# Power.net
KiCad netlist of a schematic drawn in Altium Designer
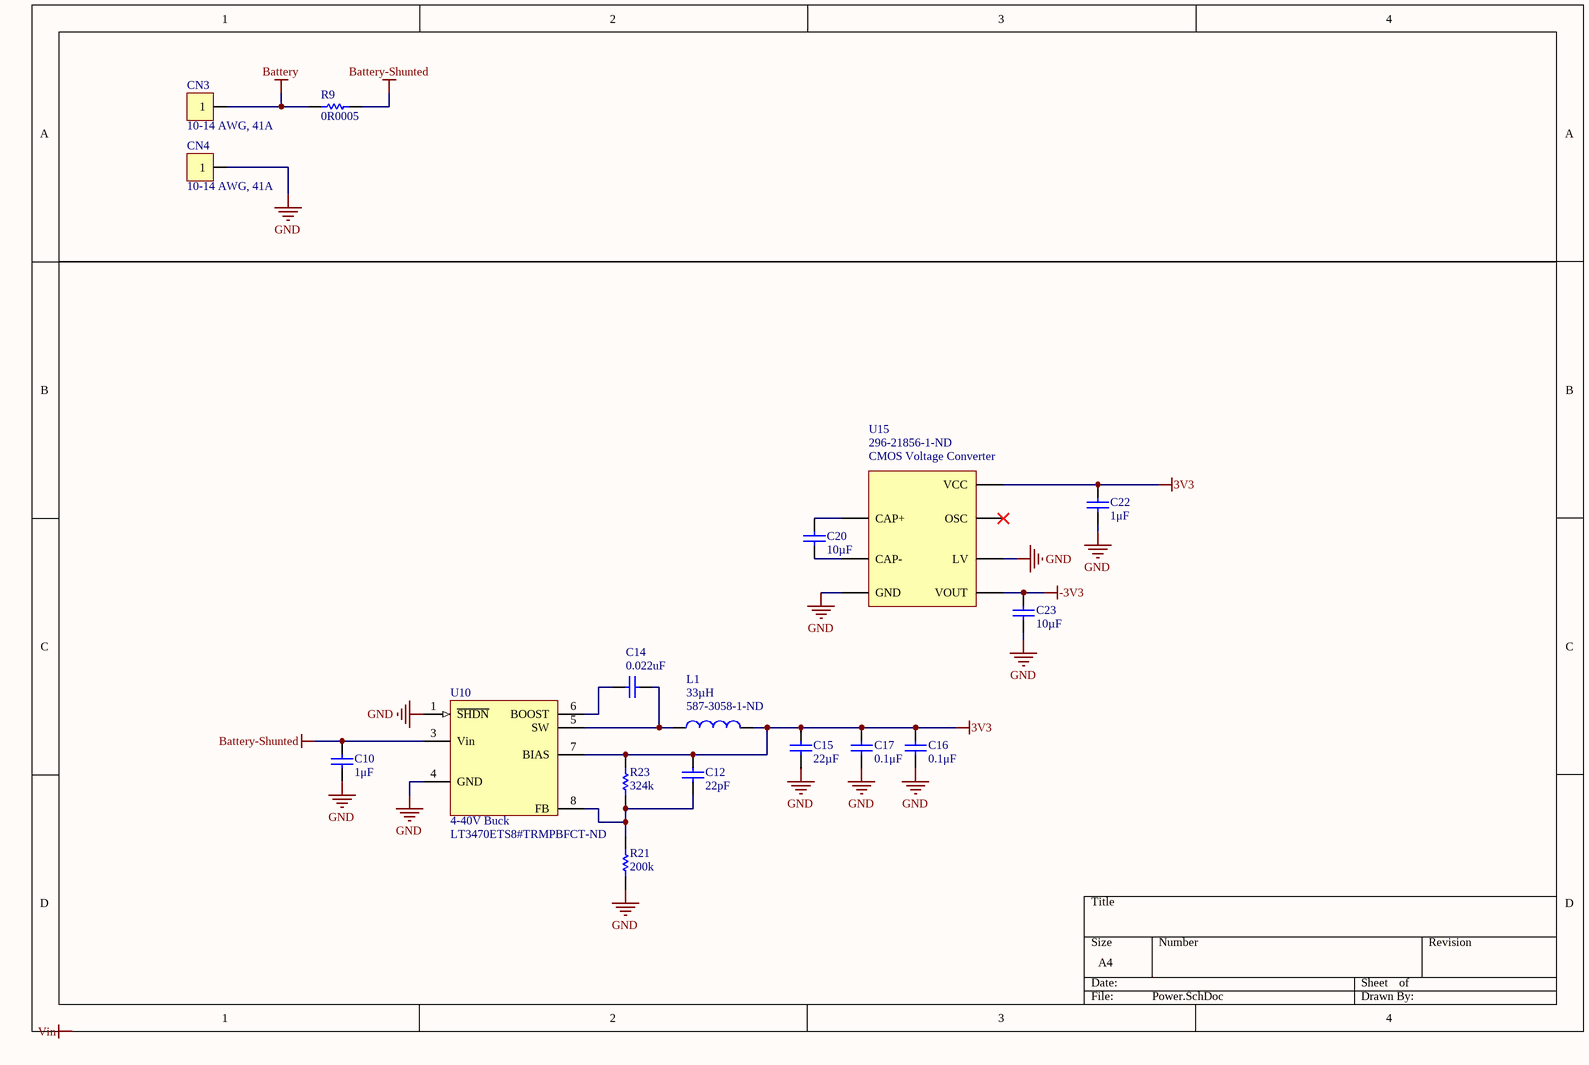
[diagram p0: Power.SchDoc]

(export (version "E")
  (design (tool "Eeschema 10.0.6"))
  (components
    (comp (ref "C10")
      (value "1μF")
      (footprint "CAPC1608N(0603\")")
      (description "Capacitor, Ceramic, 25V, +/- 10%, 0603 SMD, X5R")
      (fields
        (field (name "MFG") "Murata-Electronics-North-America")
        (field (name "PUBLISHER") "AUVic")
        (field (name "CREATED BY") "Andy Bates")
      )
      (libsource (lib "AUVic_Integrated_Library_Capacitors") (part "1uF 25V 0603 SMD, Ceramic"))
    )
    (comp (ref "C12")
      (value "22pF")
      (footprint "CAPC1608N(0603\")")
      (description "Capacitor, Ceramic, 50V, +/-5%, 0603 SMD, X7R")
      (fields (field (name "CREATED BY") "Andy Bates"))
      (libsource (lib "AUVic_Integrated_Library_Capacitors") (part "22pF 50V 0603 SMD, Ceramic"))
    )
    (comp (ref "C14")
      (value "0.022uF")
      (footprint "CAPC1608N(0603\")")
      (description "Capacitor, Ceramic, 50V, +/-10%, 0603 SMD, X7R")
      (fields (field (name "CREATED BY") "Andy Bates"))
      (libsource (lib "AUVic_Integrated_Library_Capacitors") (part "0.022uF 50V 0603 SMD, Ceramic"))
    )
    (comp (ref "C15")
      (value "22µF")
      (footprint "CAPC2012N(0805\")")
      (description "Capacitor, Ceramic, 35V, +/- 20%, 0805 SMD, X5R")
      (fields (field (name "PUBLISHER") "AUVic"))
      (libsource (lib "AUVic_Integrated_Library_Capacitors") (part "22uF 35V 0805 SMD, Ceramic"))
    )
    (comp (ref "C16")
      (value "0.1μF")
      (footprint "CAPC1608N(0603\")")
      (description "Capacitor, Ceramic, 100V, +/- 10%, 0603 SMD, X7R")
      (fields
        (field (name "MFG") "TDK")
        (field (name "PUBLISHER") "AUVic")
        (field (name "CREATED BY") "Ashwin Sira")
      )
      (libsource (lib "AUVic_Integrated_Library_Capacitors") (part "0.1uF 100V 0603 SMD, Ceramic"))
    )
    (comp (ref "C17")
      (value "0.1μF")
      (footprint "CAPC1608N(0603\")")
      (description "Capacitor, Ceramic, 100V, +/- 10%, 0603 SMD, X7R")
      (fields
        (field (name "MFG") "TDK")
        (field (name "PUBLISHER") "AUVic")
        (field (name "CREATED BY") "Ashwin Sira")
      )
      (libsource (lib "AUVic_Integrated_Library_Capacitors") (part "0.1uF 100V 0603 SMD, Ceramic"))
    )
    (comp (ref "C20")
      (value "10µF")
      (footprint "CAPC2012N(0805\")")
      (description "Capacitor, Ceramic, 10V, +/- 10%, 0805 SMD, X5R")
      (fields (field (name "PUBLISHER") "AUVic") (field (name "MADE BY") "Andy Bates"))
      (libsource (lib "AUVic_Integrated_Library_Capacitors") (part "10uF 10V 0805 SMD, Ceramic"))
    )
    (comp (ref "C22")
      (value "1μF")
      (footprint "CAPC1608N(0603\")")
      (description "Capacitor, Ceramic, 25V, +/- 10%, 0603 SMD, X5R")
      (fields
        (field (name "MFG") "Murata-Electronics-North-America")
        (field (name "PUBLISHER") "AUVic")
        (field (name "CREATED BY") "Andy Bates")
      )
      (libsource (lib "AUVic_Integrated_Library_Capacitors") (part "1uF 25V 0603 SMD, Ceramic"))
    )
    (comp (ref "C23")
      (value "10µF")
      (footprint "CAPC2012N(0805\")")
      (description "Capacitor, Ceramic, 10V, +/- 10%, 0805 SMD, X5R")
      (fields (field (name "PUBLISHER") "AUVic") (field (name "MADE BY") "Andy Bates"))
      (libsource (lib "AUVic_Integrated_Library_Capacitors") (part "10uF 10V 0805 SMD, Ceramic"))
    )
    (comp (ref "CN3")
      (value "10-14 AWG, 41A")
      (footprint "1x1, Phoenix Contact 1704837,THT")
      (description "1x1, Phoenix Contact 1704837,THT")
      (fields (field (name "PUBLISHER") "Andy Bates") (field (name "REVIEWED BY") "*"))
      (libsource (lib "AUVic_Integrated_Library_Connectors") (part "1x1, Phoenix Contact 1704837,THT"))
    )
    (comp (ref "CN4")
      (value "10-14 AWG, 41A")
      (footprint "1x1, Phoenix Contact 1704837,THT")
      (description "1x1, Phoenix Contact 1704837,THT")
      (fields (field (name "PUBLISHER") "Andy Bates") (field (name "REVIEWED BY") "*"))
      (libsource (lib "AUVic_Integrated_Library_Connectors") (part "1x1, Phoenix Contact 1704837,THT"))
    )
    (comp (ref "L1")
      (value "33µH")
      (footprint "CB - 1007 (2518)")
      (description "33µH 270mA 1.95Ohm")
      (fields
        (field (name "SUPPLIER PART NUMBER 1") "587-3058-1-ND")
        (field (name "CREATED BY") "Andy Bates")
      )
      (libsource (lib "AUVic_Integrated_Library_Inductors") (part "33µH 270mA 1.95Ohm"))
    )
    (comp (ref "R9")
      (value "0R0005")
      (footprint "RESC6332N(2512\")")
      (description "0R0005, 1%, 3W, 2512 SMD")
      (fields
        (field (name "MFG") "Riedon")
        (field (name "CREATED BY") "Ashwin Sira")
        (field (name "PUBLISHER") "AUVic")
      )
      (libsource (lib "AUVic_Integrated_Library_Resistors") (part "0R0005, 1%, 3W, 2512 SMD"))
    )
    (comp (ref "R21")
      (value "200k")
      (footprint "RESC1608N(0603\")")
      (description "200kR, 1%, 1/10W, 0603 SMD")
      (fields (field (name "MADE BY") "Ashwin Sira"))
      (libsource (lib "AUVic_Integrated_Library_Resistors") (part "200kR, 1%, 1/10W, 0603 SMD"))
    )
    (comp (ref "R23")
      (value "324k")
      (footprint "RESC1608N(0603\")")
      (description "324kR, 1%, 1/10W, 0603 SMD")
      (fields (field (name "MADE BY") "Andy Bates"))
      (libsource (lib "AUVic_Integrated_Library_Resistors") (part "324kR, 1%, 1/10W, 0603 SMD"))
    )
    (comp (ref "U10")
      (value "4-40V Buck")
      (footprint "TSOT-23-8")
      (description "Low Noise Step-Down Switching Regulator, 123-8-pin TSOT, 0 to 85 degC")
      (fields
        (field (name "MANUFACTURER") "Linear Technology")
        (field (name "SUPPLIER PART NUMBER 1") "LT3470ETS8#TRMPBFCT-ND")
      )
      (libsource (lib "AUVic_Integrated_Library_Regulators") (part "LT3470ETS8#TRMPBF"))
    )
    (comp (ref "U15")
      (value "CMOS Voltage Converter")
      (footprint "8-SOIC")
      (fields
        (field (name "MANUFACTURER PART NO.") "TL7660")
        (field (name "SUPPLIER PART NUMBER 1") "296-21856-1-ND")
        (field (name "PUBLISHER") "Altium Limited")
        (field (name "CREATED BY") "Jordan")
      )
      (libsource (lib "AUVic_Integrated_Library_Regulators") (part "TL7660"))
    )
  )
  (nets
    (net (code "1") (name "-3V3") (class "Default")
      (node (ref "C23") (pin "2") (pinfunction "Cathode_2") (pintype "passive"))
      (node (ref "U15") (pin "5") (pinfunction "VOUT_5") (pintype "passive"))
    )
    (net (code "2") (name "3V3") (class "Default")
      (node (ref "C12") (pin "1") (pinfunction "1_1") (pintype "passive"))
      (node (ref "C15") (pin "2") (pinfunction "Cathode_2") (pintype "passive"))
      (node (ref "C16") (pin "1") (pinfunction "Anode_1") (pintype "passive"))
      (node (ref "C17") (pin "1") (pinfunction "Anode_1") (pintype "passive"))
      (node (ref "C22") (pin "2") (pinfunction "Cathode_2") (pintype "passive"))
      (node (ref "L1") (pin "2") (pinfunction "2_2") (pintype "passive"))
      (node (ref "R23") (pin "2") (pinfunction "2_2") (pintype "passive"))
      (node (ref "U10") (pin "7") (pinfunction "BIAS_7") (pintype "passive"))
      (node (ref "U15") (pin "8") (pinfunction "VCC_8") (pintype "passive"))
    )
    (net (code "3") (name "Battery") (class "Default")
      (node (ref "CN3") (pin "1") (pinfunction "1_1") (pintype "passive"))
      (node (ref "R9") (pin "1") (pinfunction "1_1") (pintype "passive"))
    )
    (net (code "4") (name "Battery-Shunted") (class "Default")
      (node (ref "C10") (pin "2") (pinfunction "Cathode_2") (pintype "passive"))
      (node (ref "R9") (pin "2") (pinfunction "2_2") (pintype "passive"))
      (node (ref "U10") (pin "3") (pinfunction "Vin_3") (pintype "power_in"))
    )
    (net (code "5") (name "GND") (class "Default")
      (node (ref "C10") (pin "1") (pinfunction "Anode_1") (pintype "passive"))
      (node (ref "C15") (pin "1") (pinfunction "Anode_1") (pintype "passive"))
      (node (ref "C16") (pin "2") (pinfunction "Cathode_2") (pintype "passive"))
      (node (ref "C17") (pin "2") (pinfunction "Cathode_2") (pintype "passive"))
      (node (ref "C22") (pin "1") (pinfunction "Anode_1") (pintype "passive"))
      (node (ref "C23") (pin "1") (pinfunction "Anode_1") (pintype "passive"))
      (node (ref "CN4") (pin "1") (pinfunction "1_1") (pintype "passive"))
      (node (ref "R21") (pin "1") (pinfunction "1_1") (pintype "passive"))
      (node (ref "U10") (pin "1") (pinfunction "~{SHDN}_1") (pintype "input"))
      (node (ref "U10") (pin "4") (pinfunction "GND_4") (pintype "power_in"))
      (node (ref "U15") (pin "3") (pinfunction "GND_3") (pintype "passive"))
      (node (ref "U15") (pin "6") (pinfunction "LV_6") (pintype "passive"))
    )
    (net (code "6") (name "Net-(C20-Anode)") (class "Default")
      (node (ref "C20") (pin "1") (pinfunction "Anode_1") (pintype "passive"))
      (node (ref "U15") (pin "4") (pinfunction "CAP-_4") (pintype "passive"))
    )
    (net (code "7") (name "Net-(C20-Cathode)") (class "Default")
      (node (ref "C20") (pin "2") (pinfunction "Cathode_2") (pintype "passive"))
      (node (ref "U15") (pin "2") (pinfunction "CAP+_2") (pintype "passive"))
    )
    (net (code "8") (name "Net-(U10-BOOST)") (class "Default")
      (node (ref "C14") (pin "1") (pinfunction "1_1") (pintype "passive"))
      (node (ref "U10") (pin "6") (pinfunction "BOOST_6") (pintype "passive"))
    )
    (net (code "9") (name "Net-(U10-FB)") (class "Default")
      (node (ref "C12") (pin "2") (pinfunction "2_2") (pintype "passive"))
      (node (ref "R21") (pin "2") (pinfunction "2_2") (pintype "passive"))
      (node (ref "R23") (pin "1") (pinfunction "1_1") (pintype "passive"))
      (node (ref "U10") (pin "8") (pinfunction "FB_8") (pintype "passive"))
    )
    (net (code "10") (name "Net-(U10-SW)") (class "Default")
      (node (ref "C14") (pin "2") (pinfunction "2_2") (pintype "passive"))
      (node (ref "L1") (pin "1") (pinfunction "1_1") (pintype "passive"))
      (node (ref "U10") (pin "5") (pinfunction "SW_5") (pintype "passive"))
    )
    (net (code "12") (name "unconnected-(U15-OSC-Pad7)") (class "Default")
      (node (ref "U15") (pin "7") (pinfunction "OSC_7") (pintype "passive+no_connect"))
    )
  )
)
